# XT-02_Eyecillator.net
KiCad netlist of a schematic drawn in EAGLE
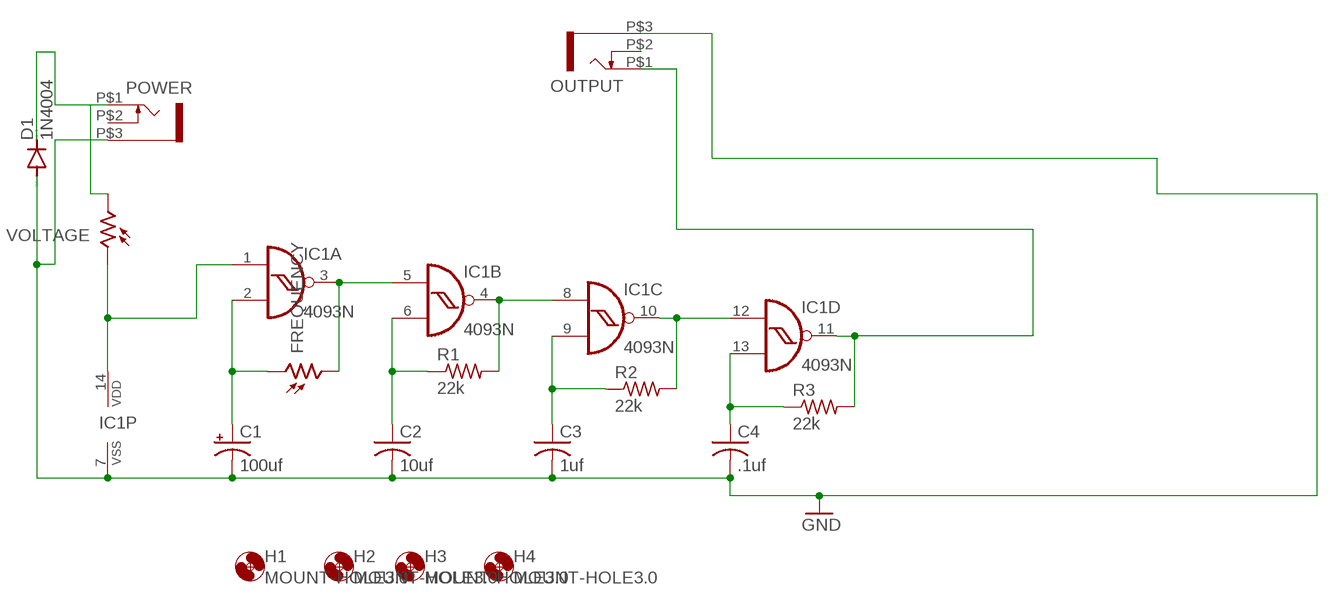
[diagram p0: schematic, sheet 1]

(export (version "E")
  (design (tool "Eeschema 10.0.6"))
  (components
    (comp (ref "C1")
      (value "100uf")
      (footprint "eagle-import:E2,5-6E")
      (libsource (lib "eagle-import") (part "CPOL-USE2,5-6E"))
    )
    (comp (ref "C2")
      (value "10uf")
      (footprint "eagle-import:C050-025X075")
      (libsource (lib "eagle-import") (part "C-US050-025X075"))
    )
    (comp (ref "C3")
      (value "1uf")
      (footprint "eagle-import:C050-025X075")
      (libsource (lib "eagle-import") (part "C-US050-025X075"))
    )
    (comp (ref "C4")
      (value ".1uf")
      (footprint "eagle-import:C050-025X075")
      (libsource (lib "eagle-import") (part "C-US050-025X075"))
    )
    (comp (ref "D1")
      (value "1N4004")
      (footprint "eagle-import:DO41-10")
      (libsource (lib "eagle-import") (part "1N4004"))
    )
    (comp (ref "FREQUENCY")
      (value "VT90N1")
      (footprint "eagle-import:VT900")
      (libsource (lib "eagle-import") (part "VT90N1"))
    )
    (comp (ref "H1")
      (value "MOUNT-HOLE3.0")
      (footprint "eagle-import:3,0")
      (libsource (lib "eagle-import") (part "MOUNT-HOLE3.0"))
    )
    (comp (ref "H2")
      (value "MOUNT-HOLE3.0")
      (footprint "eagle-import:3,0")
      (libsource (lib "eagle-import") (part "MOUNT-HOLE3.0"))
    )
    (comp (ref "H3")
      (value "MOUNT-HOLE3.0")
      (footprint "eagle-import:3,0")
      (libsource (lib "eagle-import") (part "MOUNT-HOLE3.0"))
    )
    (comp (ref "H4")
      (value "MOUNT-HOLE3.0")
      (footprint "eagle-import:3,0")
      (libsource (lib "eagle-import") (part "MOUNT-HOLE3.0"))
    )
    (comp (ref "IC1")
      (value "4093N")
      (footprint "eagle-import:DIL14")
      (libsource (lib "eagle-import") (part "4093N"))
    )
    (comp (ref "OUTPUT")
      (value "WQP-PJ301M-12_JACK")
      (footprint "eagle-import:WQP-PJ301M-12_JACK")
      (libsource (lib "eagle-import") (part "WQP-PJ301M-12_JACK"))
    )
    (comp (ref "POWER")
      (value "WQP-PJ301M-12_JACK")
      (footprint "eagle-import:WQP-PJ301M-12_JACK")
      (libsource (lib "eagle-import") (part "WQP-PJ301M-12_JACK"))
    )
    (comp (ref "R1")
      (value "22k")
      (footprint "eagle-import:0207_7")
      (libsource (lib "eagle-import") (part "R-US_0207/7"))
    )
    (comp (ref "R2")
      (value "22k")
      (footprint "eagle-import:0207_7")
      (libsource (lib "eagle-import") (part "R-US_0207/7"))
    )
    (comp (ref "R3")
      (value "22k")
      (footprint "eagle-import:0207_7")
      (libsource (lib "eagle-import") (part "R-US_0207/7"))
    )
    (comp (ref "VOLTAGE")
      (value "VT90N1")
      (footprint "eagle-import:VT900")
      (libsource (lib "eagle-import") (part "VT90N1"))
    )
  )
  (nets
    (net (code "1") (name "GND") (class "Default")
      (node (ref "C1") (pin "-") (pinfunction "-_-") (pintype "passive"))
      (node (ref "C2") (pin "2") (pinfunction "2_2") (pintype "passive"))
      (node (ref "C3") (pin "2") (pinfunction "2_2") (pintype "passive"))
      (node (ref "C4") (pin "2") (pinfunction "2_2") (pintype "passive"))
      (node (ref "D1") (pin "A") (pinfunction "A_A") (pintype "passive"))
      (node (ref "IC1") (pin "7") (pinfunction "VSS_7") (pintype "power_in"))
      (node (ref "OUTPUT") (pin "P$3") (pinfunction "1_P$3") (pintype "passive"))
      (node (ref "POWER") (pin "P$3") (pinfunction "1_P$3") (pintype "passive"))
    )
    (net (code "2") (name "Net-(IC1A-I0)") (class "Default")
      (node (ref "IC1") (pin "1") (pinfunction "I0_1") (pintype "input"))
      (node (ref "IC1") (pin "14") (pinfunction "VDD_14") (pintype "power_in"))
      (node (ref "VOLTAGE") (pin "1") (pinfunction "1_1") (pintype "passive"))
    )
    (net (code "3") (name "Net-(IC1A-I1)") (class "Default")
      (node (ref "C1") (pin "+") (pinfunction "+_+") (pintype "passive"))
      (node (ref "FREQUENCY") (pin "1") (pinfunction "1_1") (pintype "passive"))
      (node (ref "IC1") (pin "2") (pinfunction "I1_2") (pintype "input"))
    )
    (net (code "4") (name "Net-(IC1A-O)") (class "Default")
      (node (ref "FREQUENCY") (pin "2") (pinfunction "2_2") (pintype "passive"))
      (node (ref "IC1") (pin "3") (pinfunction "O_3") (pintype "output"))
      (node (ref "IC1") (pin "5") (pinfunction "I0_5") (pintype "input"))
    )
    (net (code "5") (name "Net-(IC1B-I1)") (class "Default")
      (node (ref "C2") (pin "1") (pinfunction "1_1") (pintype "passive"))
      (node (ref "IC1") (pin "6") (pinfunction "I1_6") (pintype "input"))
      (node (ref "R1") (pin "1") (pinfunction "1_1") (pintype "passive"))
    )
    (net (code "6") (name "Net-(IC1B-O)") (class "Default")
      (node (ref "IC1") (pin "4") (pinfunction "O_4") (pintype "output"))
      (node (ref "IC1") (pin "8") (pinfunction "I0_8") (pintype "input"))
      (node (ref "R1") (pin "2") (pinfunction "2_2") (pintype "passive"))
    )
    (net (code "7") (name "Net-(IC1C-I1)") (class "Default")
      (node (ref "C3") (pin "1") (pinfunction "1_1") (pintype "passive"))
      (node (ref "IC1") (pin "9") (pinfunction "I1_9") (pintype "input"))
      (node (ref "R2") (pin "1") (pinfunction "1_1") (pintype "passive"))
    )
    (net (code "8") (name "Net-(IC1C-O)") (class "Default")
      (node (ref "IC1") (pin "10") (pinfunction "O_10") (pintype "output"))
      (node (ref "IC1") (pin "12") (pinfunction "I0_12") (pintype "input"))
      (node (ref "R2") (pin "2") (pinfunction "2_2") (pintype "passive"))
    )
    (net (code "9") (name "Net-(IC1D-I1)") (class "Default")
      (node (ref "C4") (pin "1") (pinfunction "1_1") (pintype "passive"))
      (node (ref "IC1") (pin "13") (pinfunction "I1_13") (pintype "input"))
      (node (ref "R3") (pin "1") (pinfunction "1_1") (pintype "passive"))
    )
    (net (code "10") (name "Net-(IC1D-O)") (class "Default")
      (node (ref "IC1") (pin "11") (pinfunction "O_11") (pintype "output"))
      (node (ref "OUTPUT") (pin "P$1") (pinfunction "2_P$1") (pintype "passive"))
      (node (ref "R3") (pin "2") (pinfunction "2_2") (pintype "passive"))
    )
    (net (code "11") (name "Net-(POWER-2)") (class "Default")
      (node (ref "D1") (pin "C") (pinfunction "C_C") (pintype "passive"))
      (node (ref "POWER") (pin "P$1") (pinfunction "2_P$1") (pintype "passive"))
      (node (ref "VOLTAGE") (pin "2") (pinfunction "2_2") (pintype "passive"))
    )
    (net (code "12") (name "unconnected-(OUTPUT-3-PadP$2)") (class "Default")
      (node (ref "OUTPUT") (pin "P$2") (pinfunction "3_P$2") (pintype "passive"))
    )
    (net (code "13") (name "unconnected-(POWER-3-PadP$2)") (class "Default")
      (node (ref "POWER") (pin "P$2") (pinfunction "3_P$2") (pintype "passive"))
    )
  )
)
